# Control_Unit_Schematic.net
KiCad netlist of a schematic drawn in EAGLE
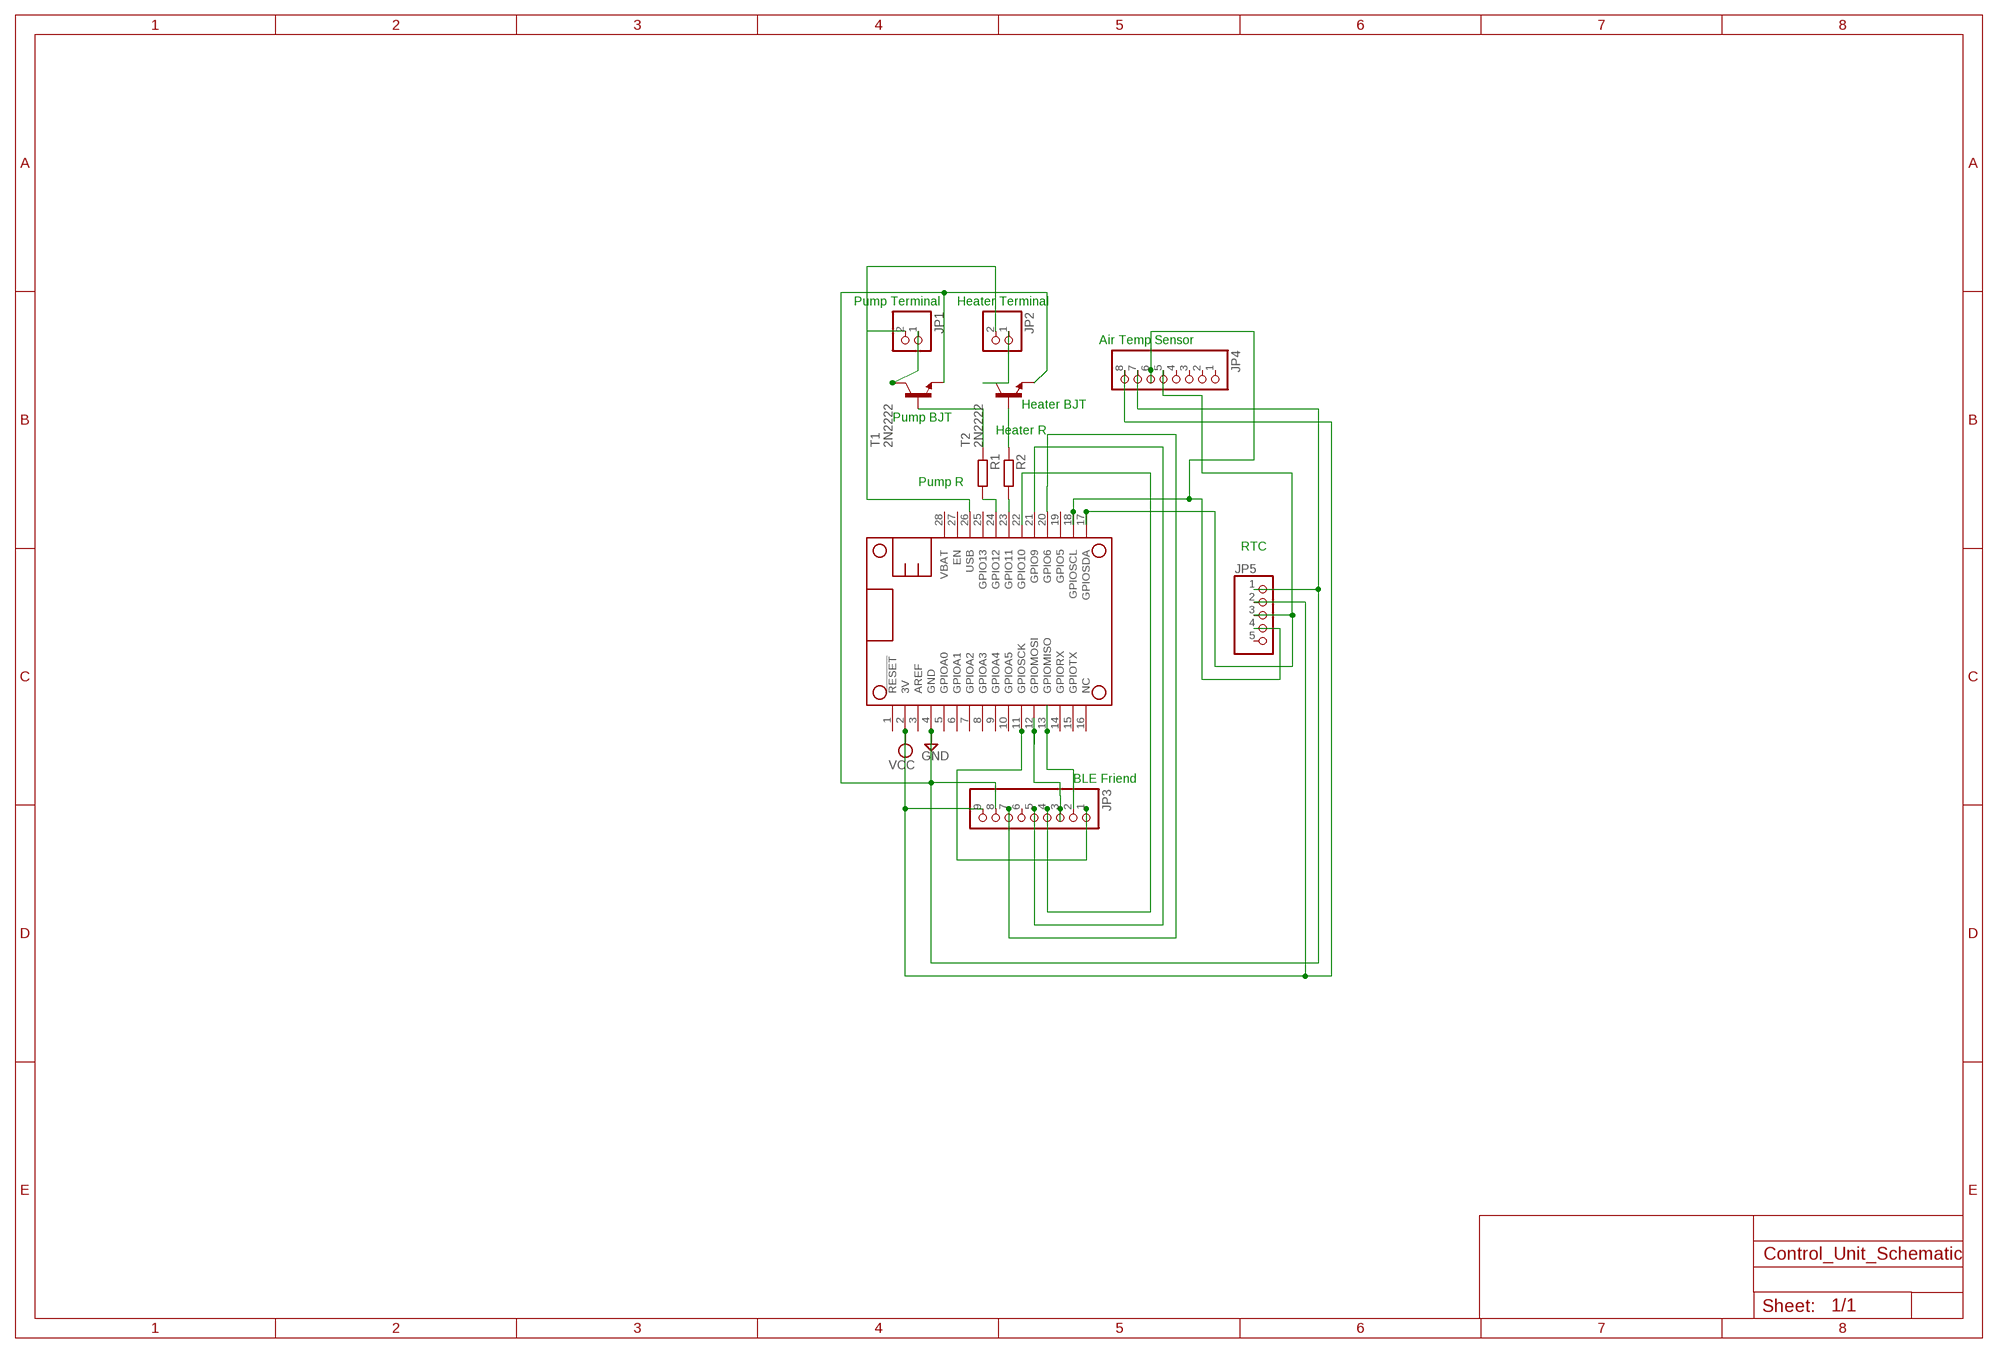
[diagram p0: schematic, sheet 1]

(export (version "E")
  (design (tool "Eeschema 10.0.6"))
  (components
    (comp (ref "JP1")
      (value "PINHD-1X2")
      (footprint "eagle-import:1X02")
      (libsource (lib "eagle-import") (part "PINHD-1X2"))
    )
    (comp (ref "JP2")
      (value "PINHD-1X2")
      (footprint "eagle-import:1X02")
      (libsource (lib "eagle-import") (part "PINHD-1X2"))
    )
    (comp (ref "JP3")
      (value "PINHD-1X9")
      (footprint "eagle-import:1X09")
      (libsource (lib "eagle-import") (part "PINHD-1X9"))
    )
    (comp (ref "JP4")
      (value "PINHD-1X8")
      (footprint "eagle-import:1X08")
      (libsource (lib "eagle-import") (part "PINHD-1X8"))
    )
    (comp (ref "JP5")
      (value "PINHD-1X5")
      (footprint "eagle-import:1X05")
      (libsource (lib "eagle-import") (part "PINHD-1X5"))
    )
    (comp (ref "MS1")
      (value "FEATHERWING_NODIM")
      (footprint "eagle-import:FEATHERWING_DIM")
      (libsource (lib "eagle-import") (part "FEATHERWING_NODIM"))
    )
    (comp (ref "R1")
      (value "R0207/10")
      (footprint "eagle-import:0207_10")
      (libsource (lib "eagle-import") (part "R0207/10"))
    )
    (comp (ref "R2")
      (value "R0207/10")
      (footprint "eagle-import:0207_10")
      (libsource (lib "eagle-import") (part "R0207/10"))
    )
    (comp (ref "T1")
      (value "2N2222")
      (footprint "eagle-import:TO92-EBC-OVAL")
      (libsource (lib "eagle-import") (part "2N2222"))
    )
    (comp (ref "T2")
      (value "2N2222")
      (footprint "eagle-import:TO92-EBC-OVAL")
      (libsource (lib "eagle-import") (part "2N2222"))
    )
  )
  (nets
    (net (code "1") (name "/VBAT") (class "Default")
      (node (ref "MS1") (pin "28") (pinfunction "VBAT_28") (pintype "power_in"))
    )
    (net (code "2") (name "GND") (class "Default")
      (node (ref "JP3") (pin "8") (pinfunction "8_8") (pintype "passive"))
      (node (ref "JP4") (pin "7") (pinfunction "7_7") (pintype "passive"))
      (node (ref "JP5") (pin "1") (pinfunction "1_1") (pintype "passive"))
      (node (ref "MS1") (pin "4") (pinfunction "GND_4") (pintype "power_in"))
      (node (ref "T1") (pin "E") (pinfunction "E_E") (pintype "passive"))
      (node (ref "T2") (pin "E") (pinfunction "E_E") (pintype "passive"))
    )
    (net (code "3") (name "Net-(JP1-Pad1)") (class "Default")
      (node (ref "JP1") (pin "1") (pinfunction "1_1") (pintype "passive"))
      (node (ref "T1") (pin "C") (pinfunction "C_C") (pintype "passive"))
    )
    (net (code "4") (name "Net-(JP2-Pad1)") (class "Default")
      (node (ref "JP2") (pin "1") (pinfunction "1_1") (pintype "passive"))
      (node (ref "T2") (pin "C") (pinfunction "C_C") (pintype "passive"))
    )
    (net (code "5") (name "Net-(MS1-GPIO6)") (class "Default")
      (node (ref "JP3") (pin "7") (pinfunction "7_7") (pintype "passive"))
      (node (ref "MS1") (pin "20") (pinfunction "GPIO6_20") (pintype "bidirectional"))
    )
    (net (code "6") (name "Net-(MS1-GPIO9)") (class "Default")
      (node (ref "JP3") (pin "5") (pinfunction "5_5") (pintype "passive"))
      (node (ref "MS1") (pin "21") (pinfunction "GPIO9_21") (pintype "bidirectional"))
    )
    (net (code "7") (name "Net-(MS1-GPIO11)") (class "Default")
      (node (ref "MS1") (pin "23") (pinfunction "GPIO11_23") (pintype "bidirectional"))
      (node (ref "R2") (pin "2") (pinfunction "2_2") (pintype "passive"))
    )
    (net (code "8") (name "Net-(MS1-GPIO12)") (class "Default")
      (node (ref "MS1") (pin "24") (pinfunction "GPIO12_24") (pintype "bidirectional"))
      (node (ref "R1") (pin "2") (pinfunction "2_2") (pintype "passive"))
    )
    (net (code "9") (name "Net-(MS1-GPIOMISO)") (class "Default")
      (node (ref "JP3") (pin "2") (pinfunction "2_2") (pintype "passive"))
      (node (ref "MS1") (pin "13") (pinfunction "GPIOMISO_13") (pintype "bidirectional"))
    )
    (net (code "10") (name "Net-(MS1-GPIOMOSI)") (class "Default")
      (node (ref "JP3") (pin "3") (pinfunction "3_3") (pintype "passive"))
      (node (ref "MS1") (pin "12") (pinfunction "GPIOMOSI_12") (pintype "bidirectional"))
    )
    (net (code "11") (name "Net-(MS1-GPIOSCK)") (class "Default")
      (node (ref "JP3") (pin "1") (pinfunction "1_1") (pintype "passive"))
      (node (ref "MS1") (pin "11") (pinfunction "GPIOSCK_11") (pintype "bidirectional"))
    )
    (net (code "12") (name "Net-(MS1-GPIOSCL)") (class "Default")
      (node (ref "JP4") (pin "6") (pinfunction "6_6") (pintype "passive"))
      (node (ref "JP5") (pin "4") (pinfunction "4_4") (pintype "passive"))
      (node (ref "MS1") (pin "18") (pinfunction "GPIOSCL_18") (pintype "bidirectional"))
    )
    (net (code "13") (name "Net-(MS1-GPIOSDA)") (class "Default")
      (node (ref "JP4") (pin "5") (pinfunction "5_5") (pintype "passive"))
      (node (ref "JP5") (pin "3") (pinfunction "3_3") (pintype "passive"))
      (node (ref "MS1") (pin "17") (pinfunction "GPIOSDA_17") (pintype "bidirectional"))
    )
    (net (code "14") (name "Net-(MS1-USB)") (class "Default")
      (node (ref "JP1") (pin "2") (pinfunction "2_2") (pintype "passive"))
      (node (ref "JP2") (pin "2") (pinfunction "2_2") (pintype "passive"))
      (node (ref "MS1") (pin "26") (pinfunction "USB_26") (pintype "power_in"))
    )
    (net (code "15") (name "Net-(R1-Pad1)") (class "Default")
      (node (ref "R1") (pin "1") (pinfunction "1_1") (pintype "passive"))
      (node (ref "T1") (pin "B") (pinfunction "B_B") (pintype "passive"))
    )
    (net (code "16") (name "Net-(R2-Pad1)") (class "Default")
      (node (ref "R2") (pin "1") (pinfunction "1_1") (pintype "passive"))
      (node (ref "T2") (pin "B") (pinfunction "B_B") (pintype "passive"))
    )
    (net (code "17") (name "VCC") (class "Default")
      (node (ref "JP3") (pin "9") (pinfunction "9_9") (pintype "passive"))
      (node (ref "JP4") (pin "8") (pinfunction "8_8") (pintype "passive"))
      (node (ref "JP5") (pin "2") (pinfunction "2_2") (pintype "passive"))
      (node (ref "MS1") (pin "2") (pinfunction "3V_2") (pintype "power_in"))
    )
    (net (code "18") (name "unconnected-(JP3-Pad4)") (class "Default")
      (node (ref "JP3") (pin "4") (pinfunction "4_4") (pintype "passive"))
    )
    (net (code "19") (name "unconnected-(JP3-Pad6)") (class "Default")
      (node (ref "JP3") (pin "6") (pinfunction "6_6") (pintype "passive"))
    )
    (net (code "20") (name "unconnected-(JP4-Pad1)") (class "Default")
      (node (ref "JP4") (pin "1") (pinfunction "1_1") (pintype "passive"))
    )
    (net (code "21") (name "unconnected-(JP4-Pad2)") (class "Default")
      (node (ref "JP4") (pin "2") (pinfunction "2_2") (pintype "passive"))
    )
    (net (code "22") (name "unconnected-(JP4-Pad3)") (class "Default")
      (node (ref "JP4") (pin "3") (pinfunction "3_3") (pintype "passive"))
    )
    (net (code "23") (name "unconnected-(JP4-Pad4)") (class "Default")
      (node (ref "JP4") (pin "4") (pinfunction "4_4") (pintype "passive"))
    )
    (net (code "24") (name "unconnected-(JP5-Pad5)") (class "Default")
      (node (ref "JP5") (pin "5") (pinfunction "5_5") (pintype "passive"))
    )
    (net (code "25") (name "unconnected-(MS1-AREF-Pad3)") (class "Default")
      (node (ref "MS1") (pin "3") (pinfunction "AREF_3") (pintype "passive"))
    )
    (net (code "26") (name "unconnected-(MS1-EN-Pad27)") (class "Default")
      (node (ref "MS1") (pin "27") (pinfunction "EN_27") (pintype "passive"))
    )
    (net (code "27") (name "unconnected-(MS1-GPIO5-Pad19)") (class "Default")
      (node (ref "MS1") (pin "19") (pinfunction "GPIO5_19") (pintype "bidirectional"))
    )
    (net (code "28") (name "unconnected-(MS1-GPIO10-Pad22)") (class "Default")
      (node (ref "MS1") (pin "22") (pinfunction "GPIO10_22") (pintype "bidirectional"))
    )
    (net (code "29") (name "unconnected-(MS1-GPIO13-Pad25)") (class "Default")
      (node (ref "MS1") (pin "25") (pinfunction "GPIO13_25") (pintype "bidirectional"))
    )
    (net (code "30") (name "unconnected-(MS1-GPIOA0-Pad5)") (class "Default")
      (node (ref "MS1") (pin "5") (pinfunction "GPIOA0_5") (pintype "bidirectional"))
    )
    (net (code "31") (name "unconnected-(MS1-GPIOA1-Pad6)") (class "Default")
      (node (ref "MS1") (pin "6") (pinfunction "GPIOA1_6") (pintype "bidirectional"))
    )
    (net (code "32") (name "unconnected-(MS1-GPIOA2-Pad7)") (class "Default")
      (node (ref "MS1") (pin "7") (pinfunction "GPIOA2_7") (pintype "bidirectional"))
    )
    (net (code "33") (name "unconnected-(MS1-GPIOA3-Pad8)") (class "Default")
      (node (ref "MS1") (pin "8") (pinfunction "GPIOA3_8") (pintype "bidirectional"))
    )
    (net (code "34") (name "unconnected-(MS1-GPIOA4-Pad9)") (class "Default")
      (node (ref "MS1") (pin "9") (pinfunction "GPIOA4_9") (pintype "bidirectional"))
    )
    (net (code "35") (name "unconnected-(MS1-GPIOA5-Pad10)") (class "Default")
      (node (ref "MS1") (pin "10") (pinfunction "GPIOA5_10") (pintype "bidirectional"))
    )
    (net (code "36") (name "unconnected-(MS1-GPIORX-Pad14)") (class "Default")
      (node (ref "MS1") (pin "14") (pinfunction "GPIORX_14") (pintype "bidirectional"))
    )
    (net (code "37") (name "unconnected-(MS1-GPIOTX-Pad15)") (class "Default")
      (node (ref "MS1") (pin "15") (pinfunction "GPIOTX_15") (pintype "bidirectional"))
    )
    (net (code "38") (name "unconnected-(MS1-NC-Pad16)") (class "Default")
      (node (ref "MS1") (pin "16") (pinfunction "NC_16") (pintype "passive"))
    )
    (net (code "39") (name "unconnected-(MS1-~{RESET}-Pad1)") (class "Default")
      (node (ref "MS1") (pin "1") (pinfunction "~{RESET}_1") (pintype "input"))
    )
  )
)
